# SCH_Sega_Pad_-_Amiga_Joystick_Autofire_2.net
KiCad netlist of a schematic drawn in EasyEDA
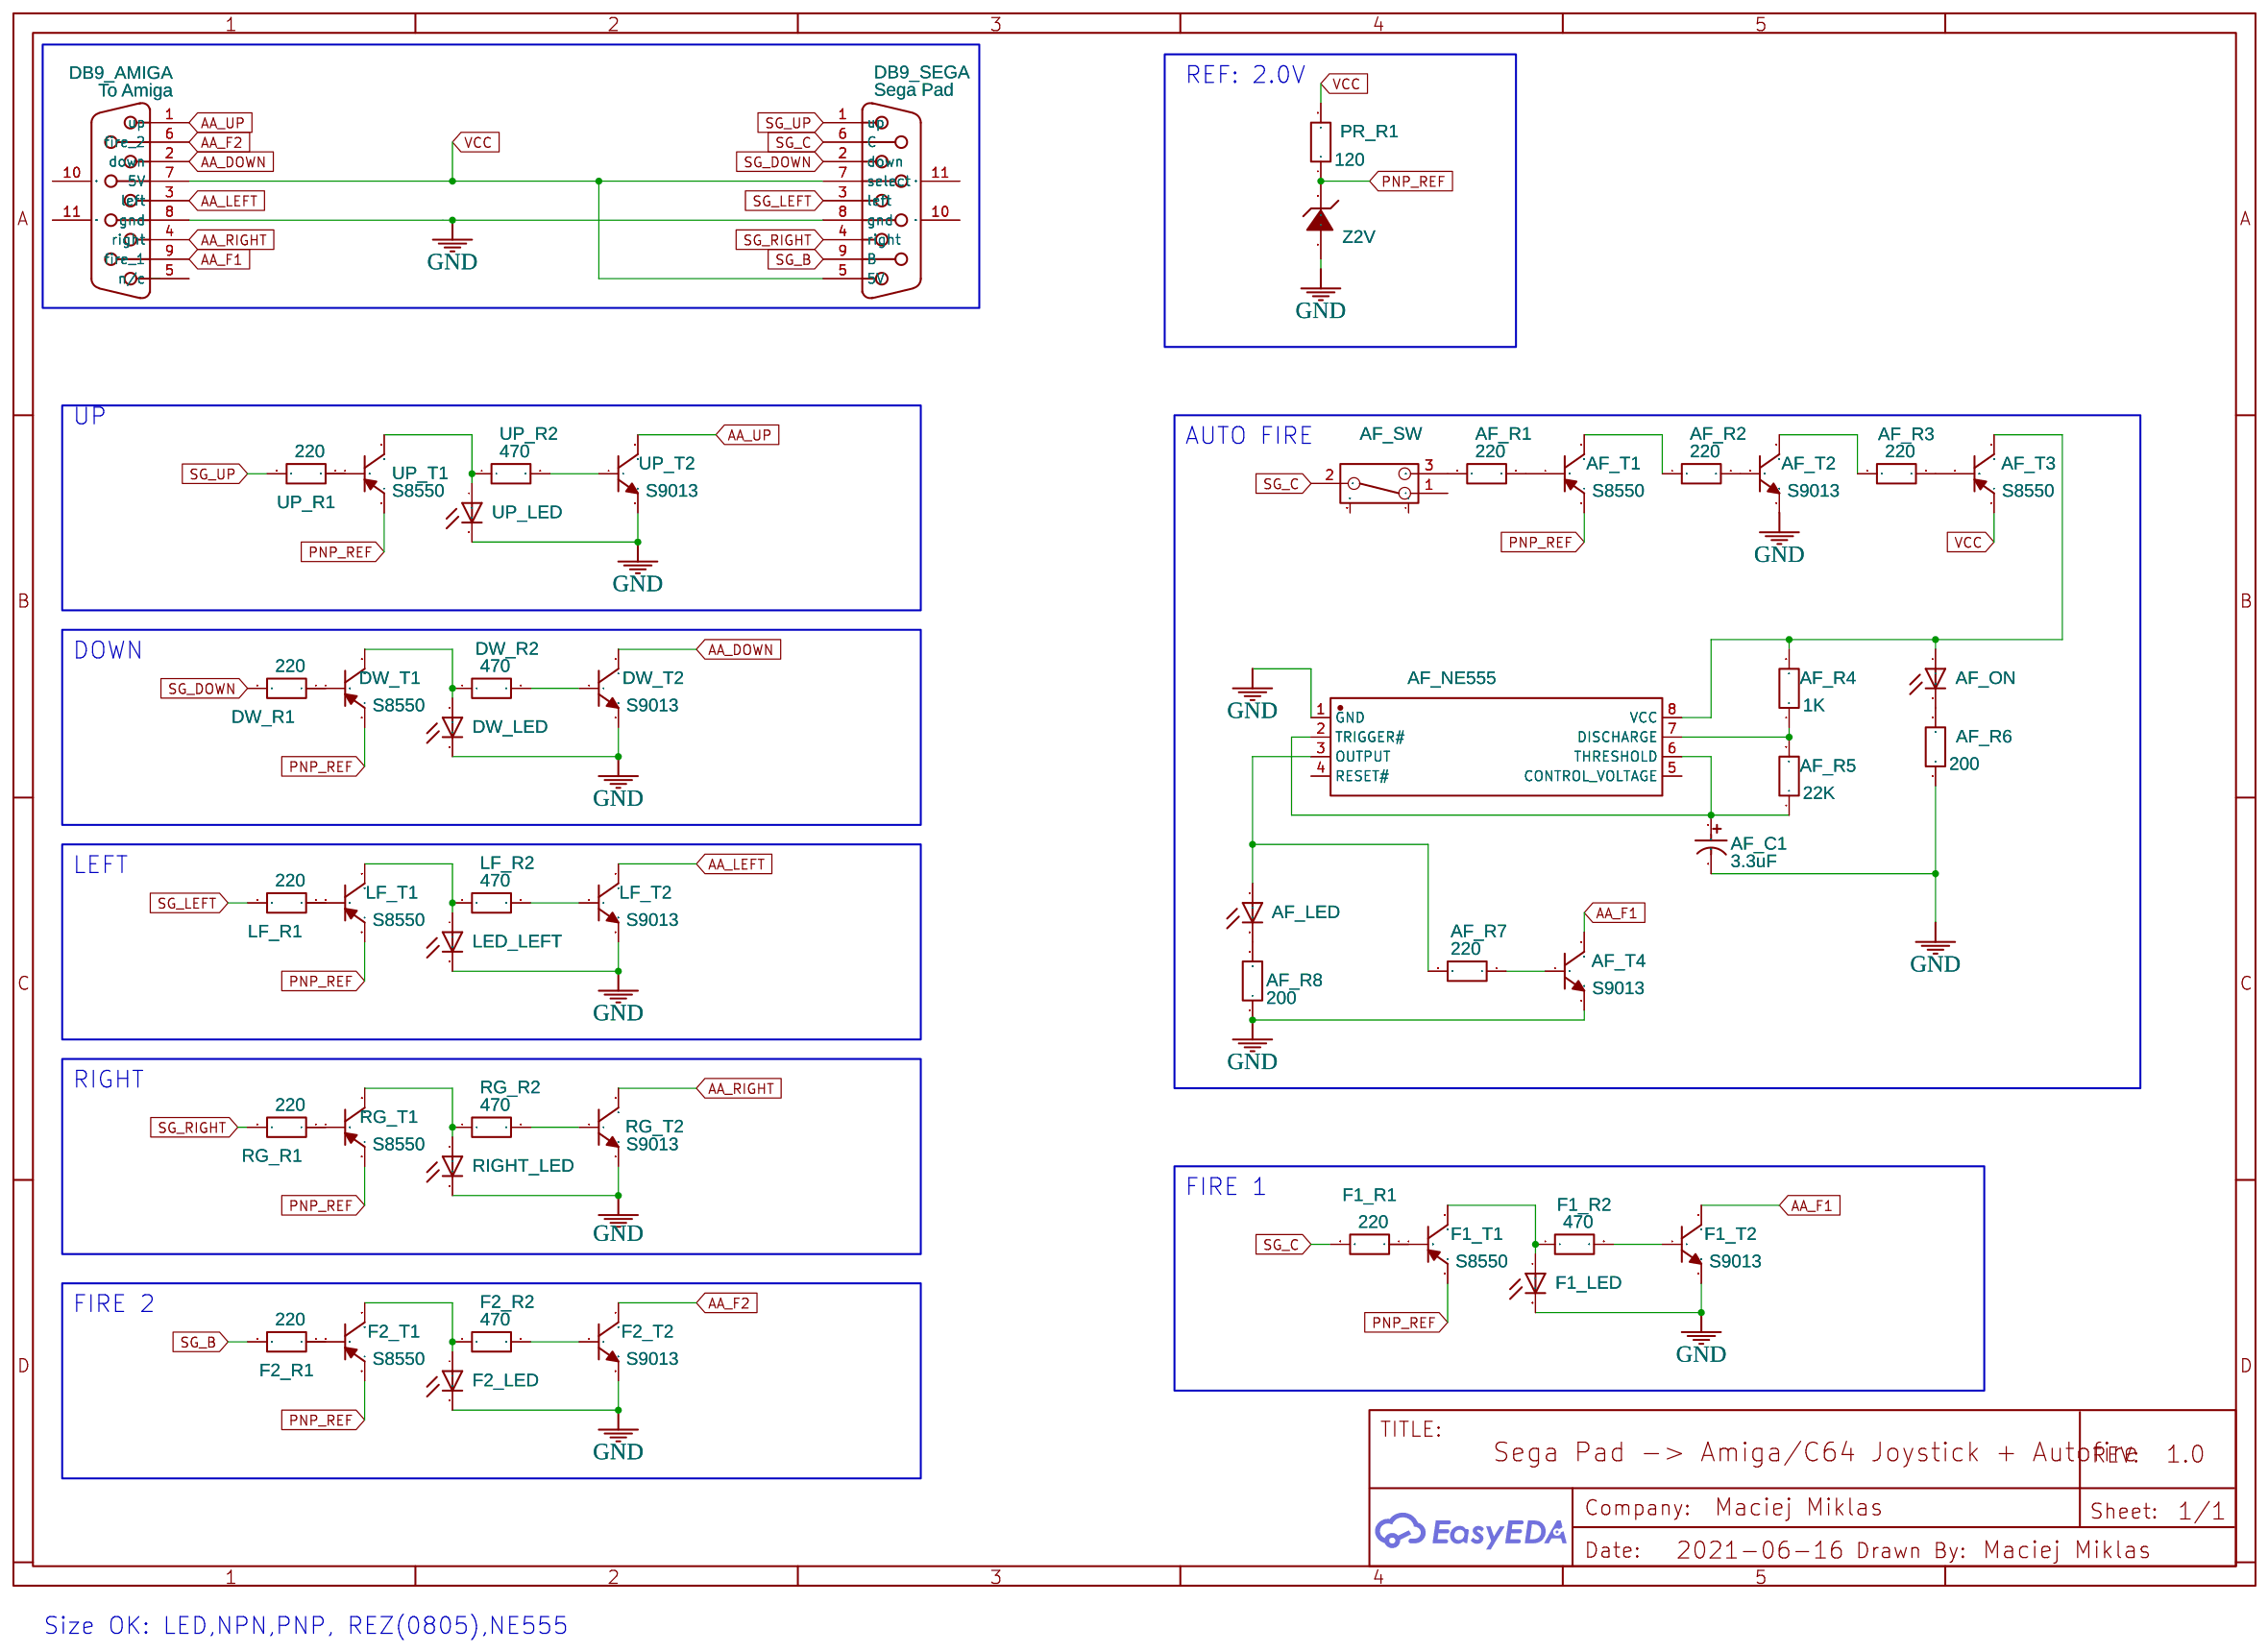
[diagram p0: schematic sheet]

(export (version "E")
  (design (tool "Eeschema 10.0.6"))
  (components
    (comp (ref "AF_555")
      (value "AF_NE555")
      (fields (field (name "BOM_Manufacturer Part") "NE555D") (field (name "BOM_Supplier Part") "C596355"))
      (libsource (lib "") (part "NE555D_C596355"))
    )
    (comp (ref "AF_C1")
      (value "3.3uF")
      (fields
        (field (name "BOM_Manufacturer Part") "3.3uF 50V 5*11")
        (field (name "BOM_Supplier Part") "C45666")
      )
      (libsource (lib "") (part "3.3uF 50V 5*11"))
    )
    (comp (ref "AF_LED") (value "LED") (libsource (lib "") (part "LED_2")))
    (comp (ref "AF_ON") (value "LED") (libsource (lib "") (part "LED_1")))
    (comp (ref "AF_R1")
      (value "220")
      (fields
        (field (name "BOM_Manufacturer Part") "WR08X102 JTL")
        (field (name "BOM_Supplier Part") "C384174")
      )
      (libsource (lib "") (part "WR08X102 JTL_7"))
    )
    (comp (ref "AF_R2")
      (value "220")
      (fields
        (field (name "BOM_Manufacturer Part") "WR08X102 JTL")
        (field (name "BOM_Supplier Part") "C384174")
      )
      (libsource (lib "") (part "WR08X102 JTL_6"))
    )
    (comp (ref "AF_R3")
      (value "220")
      (fields
        (field (name "BOM_Manufacturer Part") "WR08X102 JTL")
        (field (name "BOM_Supplier Part") "C384174")
      )
      (libsource (lib "") (part "WR08X102 JTL_6"))
    )
    (comp (ref "AF_R4")
      (value "1K")
      (fields
        (field (name "BOM_Manufacturer Part") "WR08X102 JTL")
        (field (name "BOM_Supplier Part") "C384174")
      )
      (libsource (lib "") (part "WR08X102 JTL"))
    )
    (comp (ref "AF_R5")
      (value "22K")
      (fields
        (field (name "BOM_Manufacturer Part") "WR08X102 JTL")
        (field (name "BOM_Supplier Part") "C384174")
      )
      (libsource (lib "") (part "WR08X102 JTL"))
    )
    (comp (ref "AF_R6")
      (value "200")
      (fields
        (field (name "BOM_Manufacturer Part") "WR08X102 JTL")
        (field (name "BOM_Supplier Part") "C384174")
      )
      (libsource (lib "") (part "WR08X102 JTL"))
    )
    (comp (ref "AF_R7")
      (value "220")
      (fields
        (field (name "BOM_Manufacturer Part") "WR08X102 JTL")
        (field (name "BOM_Supplier Part") "C384174")
      )
      (libsource (lib "") (part "WR08X102 JTL_7"))
    )
    (comp (ref "AF_R8")
      (value "200")
      (fields
        (field (name "BOM_Manufacturer Part") "WR08X102 JTL")
        (field (name "BOM_Supplier Part") "C384174")
      )
      (libsource (lib "") (part "WR08X102 JTL"))
    )
    (comp (ref "AF_SW") (value "AUTOFIRE ON/OFF") (libsource (lib "") (part "SW_SPDT")))
    (comp (ref "AF_T1")
      (value "S8550")
      (fields (field (name "BOM_Supplier Part") "C2828467"))
      (libsource (lib "") (part "S8550_C2828467_6"))
    )
    (comp (ref "AF_T2")
      (value "S9013")
      (fields
        (field (name "BOM_Manufacturer Part") "S9013 120-200")
        (field (name "BOM_Supplier Part") "C107404")
      )
      (libsource (lib "") (part "S9013 120-200_4"))
    )
    (comp (ref "AF_T3")
      (value "S8550")
      (fields (field (name "BOM_Supplier Part") "C2828467"))
      (libsource (lib "") (part "S8550_C2828467_6"))
    )
    (comp (ref "AF_T4")
      (value "S9013")
      (fields
        (field (name "BOM_Manufacturer Part") "S9013 120-200")
        (field (name "BOM_Supplier Part") "C107404")
      )
      (libsource (lib "") (part "S9013 120-200_4"))
    )
    (comp (ref "DB9_AMIGA")
      (value "To Amiga")
      (fields (field (name "BOM_Supplier Part") "C141882"))
      (libsource (lib "") (part "DB9_Female"))
    )
    (comp (ref "DB9_SEGA")
      (value "Sega Pad")
      (fields (field (name "BOM_Supplier Part") "C185657"))
      (libsource (lib "") (part "DB9_Male"))
    )
    (comp (ref "DW_LED") (value "LED") (libsource (lib "") (part "LED_6")))
    (comp (ref "DW_R1")
      (value "220")
      (fields
        (field (name "BOM_Manufacturer Part") "WR08X102 JTL")
        (field (name "BOM_Supplier Part") "C384174")
      )
      (libsource (lib "") (part "WR08X102 JTL_13"))
    )
    (comp (ref "DW_R2")
      (value "470")
      (fields
        (field (name "BOM_Manufacturer Part") "WR08X102 JTL")
        (field (name "BOM_Supplier Part") "C384174")
      )
      (libsource (lib "") (part "WR08X102 JTL_3"))
    )
    (comp (ref "DW_T1")
      (value "S8550")
      (fields (field (name "BOM_Supplier Part") "C2828467"))
      (libsource (lib "") (part "S8550_C2828467_5"))
    )
    (comp (ref "DW_T2")
      (value "S9013")
      (fields
        (field (name "BOM_Manufacturer Part") "S9013 120-200")
        (field (name "BOM_Supplier Part") "C107404")
      )
      (libsource (lib "") (part "S9013 120-200_6"))
    )
    (comp (ref "F1_LED") (value "LED") (libsource (lib "") (part "LED_7")))
    (comp (ref "F1_R1")
      (value "220")
      (fields
        (field (name "BOM_Manufacturer Part") "WR08X102 JTL")
        (field (name "BOM_Supplier Part") "C384174")
      )
      (libsource (lib "") (part "WR08X102 JTL_14"))
    )
    (comp (ref "F1_R2")
      (value "470")
      (fields
        (field (name "BOM_Manufacturer Part") "WR08X102 JTL")
        (field (name "BOM_Supplier Part") "C384174")
      )
      (libsource (lib "") (part "WR08X102 JTL_1"))
    )
    (comp (ref "F1_T1")
      (value "S8550")
      (fields (field (name "BOM_Supplier Part") "C2828467"))
      (libsource (lib "") (part "S8550_C2828467_4"))
    )
    (comp (ref "F1_T2")
      (value "S9013")
      (fields
        (field (name "BOM_Manufacturer Part") "S9013 120-200")
        (field (name "BOM_Supplier Part") "C107404")
      )
      (libsource (lib "") (part "S9013 120-200_5"))
    )
    (comp (ref "F2_LED") (value "LED") (libsource (lib "") (part "LED_5")))
    (comp (ref "F2_R1")
      (value "220")
      (fields
        (field (name "BOM_Manufacturer Part") "WR08X102 JTL")
        (field (name "BOM_Supplier Part") "C384174")
      )
      (libsource (lib "") (part "WR08X102 JTL_8"))
    )
    (comp (ref "F2_R2")
      (value "470")
      (fields
        (field (name "BOM_Manufacturer Part") "WR08X102 JTL")
        (field (name "BOM_Supplier Part") "C384174")
      )
      (libsource (lib "") (part "WR08X102 JTL_2"))
    )
    (comp (ref "F2_T1")
      (value "S8550")
      (fields (field (name "BOM_Supplier Part") "C2828467"))
      (libsource (lib "") (part "S8550_C2828467_3"))
    )
    (comp (ref "F2_T2")
      (value "S9013")
      (fields
        (field (name "BOM_Manufacturer Part") "S9013 120-200")
        (field (name "BOM_Supplier Part") "C107404")
      )
      (libsource (lib "") (part "S9013 120-200_2"))
    )
    (comp (ref "LED_LEFT") (value "LED") (libsource (lib "") (part "LED_4")))
    (comp (ref "LF_R1")
      (value "220")
      (fields
        (field (name "BOM_Manufacturer Part") "WR08X102 JTL")
        (field (name "BOM_Supplier Part") "C384174")
      )
      (libsource (lib "") (part "WR08X102 JTL_12"))
    )
    (comp (ref "LF_R2")
      (value "470")
      (fields
        (field (name "BOM_Manufacturer Part") "WR08X102 JTL")
        (field (name "BOM_Supplier Part") "C384174")
      )
      (libsource (lib "") (part "WR08X102 JTL_9"))
    )
    (comp (ref "LF_T1")
      (value "S8550")
      (fields (field (name "BOM_Supplier Part") "C2828467"))
      (libsource (lib "") (part "S8550_C2828467"))
    )
    (comp (ref "LF_T2")
      (value "S9013")
      (fields
        (field (name "BOM_Manufacturer Part") "S9013 120-200")
        (field (name "BOM_Supplier Part") "C107404")
      )
      (libsource (lib "") (part "S9013 120-200_1"))
    )
    (comp (ref "PR_D1")
      (value "Z2V")
      (fields (field (name "BOM_Manufacturer Part") "ZMM2V0") (field (name "BOM_Supplier Part") "C8079"))
      (libsource (lib "") (part "ZMM2V0"))
    )
    (comp (ref "PR_R1")
      (value "120")
      (fields
        (field (name "BOM_Manufacturer Part") "WR08X102 JTL")
        (field (name "BOM_Supplier Part") "C384174")
      )
      (libsource (lib "") (part "WR08X102 JTL_10"))
    )
    (comp (ref "RG_R1")
      (value "220")
      (fields
        (field (name "BOM_Manufacturer Part") "WR08X102 JTL")
        (field (name "BOM_Supplier Part") "C384174")
      )
      (libsource (lib "") (part "WR08X102 JTL_5"))
    )
    (comp (ref "RG_R2")
      (value "470")
      (fields
        (field (name "BOM_Manufacturer Part") "WR08X102 JTL")
        (field (name "BOM_Supplier Part") "C384174")
      )
      (libsource (lib "") (part "WR08X102 JTL_11"))
    )
    (comp (ref "RG_T1")
      (value "S8550")
      (fields (field (name "BOM_Supplier Part") "C2828467"))
      (libsource (lib "") (part "S8550_C2828467_1"))
    )
    (comp (ref "RG_T2")
      (value "S9013")
      (fields
        (field (name "BOM_Manufacturer Part") "S9013 120-200")
        (field (name "BOM_Supplier Part") "C107404")
      )
      (libsource (lib "") (part "S9013 120-200"))
    )
    (comp (ref "RIGHT_LED") (value "LED") (libsource (lib "") (part "LED")))
    (comp (ref "UP_LED") (value "LED") (libsource (lib "") (part "LED_3")))
    (comp (ref "UP_R1")
      (value "220")
      (fields
        (field (name "BOM_Manufacturer Part") "WR08X102 JTL")
        (field (name "BOM_Supplier Part") "C384174")
      )
      (libsource (lib "") (part "WR08X102 JTL_15"))
    )
    (comp (ref "UP_R2")
      (value "470")
      (fields
        (field (name "BOM_Manufacturer Part") "WR08X102 JTL")
        (field (name "BOM_Supplier Part") "C384174")
      )
      (libsource (lib "") (part "WR08X102 JTL_4"))
    )
    (comp (ref "UP_T1")
      (value "S8550")
      (fields (field (name "BOM_Supplier Part") "C2828467"))
      (libsource (lib "") (part "S8550_C2828467_2"))
    )
    (comp (ref "UP_T2")
      (value "S9013")
      (fields
        (field (name "BOM_Manufacturer Part") "S9013 120-200")
        (field (name "BOM_Supplier Part") "C107404")
      )
      (libsource (lib "") (part "S9013 120-200_3"))
    )
  )
  (nets
    (net (code "1") (name "AA_DOWN") (class "Default")
      (node (ref "DB9_AMIGA") (pin "2") (pinfunction "down_2") (pintype "input"))
      (node (ref "DW_T2") (pin "3") (pinfunction "3_3") (pintype "input"))
    )
    (net (code "2") (name "AA_F1") (class "Default")
      (node (ref "AF_T4") (pin "3") (pinfunction "3_3") (pintype "input"))
      (node (ref "DB9_AMIGA") (pin "9") (pinfunction "fire_1_9") (pintype "input"))
      (node (ref "F1_T2") (pin "3") (pinfunction "3_3") (pintype "input"))
    )
    (net (code "3") (name "AA_F2") (class "Default")
      (node (ref "DB9_AMIGA") (pin "6") (pinfunction "fire_2_6") (pintype "input"))
      (node (ref "F2_T2") (pin "3") (pinfunction "3_3") (pintype "input"))
    )
    (net (code "4") (name "AA_LEFT") (class "Default")
      (node (ref "DB9_AMIGA") (pin "3") (pinfunction "left_3") (pintype "input"))
      (node (ref "LF_T2") (pin "3") (pinfunction "3_3") (pintype "input"))
    )
    (net (code "5") (name "AA_RIGHT") (class "Default")
      (node (ref "DB9_AMIGA") (pin "4") (pinfunction "right_4") (pintype "input"))
      (node (ref "RG_T2") (pin "3") (pinfunction "3_3") (pintype "input"))
    )
    (net (code "6") (name "AA_UP") (class "Default")
      (node (ref "DB9_AMIGA") (pin "1") (pinfunction "up_1") (pintype "input"))
      (node (ref "UP_T2") (pin "3") (pinfunction "3_3") (pintype "input"))
    )
    (net (code "7") (name "GND") (class "Default")
      (node (ref "AF_555") (pin "1") (pinfunction "GND_1") (pintype "unspecified"))
      (node (ref "AF_C1") (pin "2") (pinfunction "2_2") (pintype "input"))
      (node (ref "AF_R6") (pin "1") (pinfunction "1_1") (pintype "unspecified"))
      (node (ref "AF_R8") (pin "1") (pinfunction "1_1") (pintype "unspecified"))
      (node (ref "AF_T2") (pin "2") (pinfunction "2_2") (pintype "input"))
      (node (ref "AF_T4") (pin "2") (pinfunction "2_2") (pintype "input"))
      (node (ref "DB9_AMIGA") (pin "8") (pinfunction "gnd_8") (pintype "input"))
      (node (ref "DB9_SEGA") (pin "8") (pinfunction "gnd_8") (pintype "input"))
      (node (ref "DW_LED") (pin "C") (pinfunction "C_C") (pintype "unspecified"))
      (node (ref "DW_T2") (pin "2") (pinfunction "2_2") (pintype "input"))
      (node (ref "F1_LED") (pin "C") (pinfunction "C_C") (pintype "unspecified"))
      (node (ref "F1_T2") (pin "2") (pinfunction "2_2") (pintype "input"))
      (node (ref "F2_LED") (pin "C") (pinfunction "C_C") (pintype "unspecified"))
      (node (ref "F2_T2") (pin "2") (pinfunction "2_2") (pintype "input"))
      (node (ref "LED_LEFT") (pin "C") (pinfunction "C_C") (pintype "unspecified"))
      (node (ref "LF_T2") (pin "2") (pinfunction "2_2") (pintype "input"))
      (node (ref "PR_D1") (pin "2") (pinfunction "A_2") (pintype "unspecified"))
      (node (ref "RG_T2") (pin "2") (pinfunction "2_2") (pintype "input"))
      (node (ref "RIGHT_LED") (pin "C") (pinfunction "C_C") (pintype "unspecified"))
      (node (ref "UP_LED") (pin "C") (pinfunction "C_C") (pintype "unspecified"))
      (node (ref "UP_T2") (pin "2") (pinfunction "2_2") (pintype "input"))
    )
    (net (code "8") (name "Net-(AF_555-DISCHARGE)") (class "Default")
      (node (ref "AF_555") (pin "7") (pinfunction "DISCHARGE_7") (pintype "unspecified"))
      (node (ref "AF_R4") (pin "1") (pinfunction "1_1") (pintype "unspecified"))
      (node (ref "AF_R5") (pin "2") (pinfunction "2_2") (pintype "unspecified"))
    )
    (net (code "9") (name "Net-(AF_555-OUTPUT)") (class "Default")
      (node (ref "AF_555") (pin "3") (pinfunction "OUTPUT_3") (pintype "unspecified"))
      (node (ref "AF_LED") (pin "A") (pinfunction "A_A") (pintype "unspecified"))
      (node (ref "AF_R7") (pin "2") (pinfunction "2_2") (pintype "unspecified"))
    )
    (net (code "10") (name "Net-(AF_555-THRESHOLD)") (class "Default")
      (node (ref "AF_555") (pin "2") (pinfunction "TRIGGER#_2") (pintype "unspecified"))
      (node (ref "AF_555") (pin "6") (pinfunction "THRESHOLD_6") (pintype "unspecified"))
      (node (ref "AF_C1") (pin "1") (pinfunction "1_1") (pintype "input"))
      (node (ref "AF_R5") (pin "1") (pinfunction "1_1") (pintype "unspecified"))
    )
    (net (code "11") (name "Net-(AF_555-VCC)") (class "Default")
      (node (ref "AF_555") (pin "8") (pinfunction "VCC_8") (pintype "unspecified"))
      (node (ref "AF_ON") (pin "A") (pinfunction "A_A") (pintype "unspecified"))
      (node (ref "AF_R4") (pin "2") (pinfunction "2_2") (pintype "unspecified"))
      (node (ref "AF_T3") (pin "3") (pinfunction "C_3") (pintype "unspecified"))
    )
    (net (code "12") (name "Net-(AF_LED-PadC)") (class "Default")
      (node (ref "AF_LED") (pin "C") (pinfunction "C_C") (pintype "unspecified"))
      (node (ref "AF_R8") (pin "2") (pinfunction "2_2") (pintype "unspecified"))
    )
    (net (code "13") (name "Net-(AF_ON-PadC)") (class "Default")
      (node (ref "AF_ON") (pin "C") (pinfunction "C_C") (pintype "unspecified"))
      (node (ref "AF_R6") (pin "2") (pinfunction "2_2") (pintype "unspecified"))
    )
    (net (code "14") (name "Net-(AF_R1-Pad2)") (class "Default")
      (node (ref "AF_R1") (pin "2") (pinfunction "2_2") (pintype "unspecified"))
      (node (ref "AF_SW") (pin "3") (pinfunction "3_3") (pintype "unspecified"))
    )
    (net (code "15") (name "Net-(AF_R2-Pad2)") (class "Default")
      (node (ref "AF_R2") (pin "2") (pinfunction "2_2") (pintype "unspecified"))
      (node (ref "AF_T2") (pin "1") (pinfunction "1_1") (pintype "input"))
    )
    (net (code "16") (name "Net-(AF_R3-Pad1)") (class "Default")
      (node (ref "AF_R3") (pin "1") (pinfunction "1_1") (pintype "unspecified"))
      (node (ref "AF_T2") (pin "3") (pinfunction "3_3") (pintype "input"))
    )
    (net (code "17") (name "Net-(AF_R7-Pad1)") (class "Default")
      (node (ref "AF_R7") (pin "1") (pinfunction "1_1") (pintype "unspecified"))
      (node (ref "AF_T4") (pin "1") (pinfunction "1_1") (pintype "input"))
    )
    (net (code "18") (name "Net-(AF_T1-B)") (class "Default")
      (node (ref "AF_R1") (pin "1") (pinfunction "1_1") (pintype "unspecified"))
      (node (ref "AF_T1") (pin "1") (pinfunction "B_1") (pintype "unspecified"))
    )
    (net (code "19") (name "Net-(AF_T1-C)") (class "Default")
      (node (ref "AF_R2") (pin "1") (pinfunction "1_1") (pintype "unspecified"))
      (node (ref "AF_T1") (pin "3") (pinfunction "C_3") (pintype "unspecified"))
    )
    (net (code "20") (name "Net-(AF_T3-B)") (class "Default")
      (node (ref "AF_R3") (pin "2") (pinfunction "2_2") (pintype "unspecified"))
      (node (ref "AF_T3") (pin "1") (pinfunction "B_1") (pintype "unspecified"))
    )
    (net (code "21") (name "Net-(DW_R2-Pad2)") (class "Default")
      (node (ref "DW_R2") (pin "2") (pinfunction "2_2") (pintype "unspecified"))
      (node (ref "DW_T2") (pin "1") (pinfunction "1_1") (pintype "input"))
    )
    (net (code "22") (name "Net-(DW_T1-B)") (class "Default")
      (node (ref "DW_R1") (pin "1") (pinfunction "1_1") (pintype "unspecified"))
      (node (ref "DW_T1") (pin "1") (pinfunction "B_1") (pintype "unspecified"))
    )
    (net (code "23") (name "Net-(DW_T1-C)") (class "Default")
      (node (ref "DW_LED") (pin "A") (pinfunction "A_A") (pintype "unspecified"))
      (node (ref "DW_R2") (pin "1") (pinfunction "1_1") (pintype "unspecified"))
      (node (ref "DW_T1") (pin "3") (pinfunction "C_3") (pintype "unspecified"))
    )
    (net (code "24") (name "Net-(F1_R2-Pad2)") (class "Default")
      (node (ref "F1_R2") (pin "2") (pinfunction "2_2") (pintype "unspecified"))
      (node (ref "F1_T2") (pin "1") (pinfunction "1_1") (pintype "input"))
    )
    (net (code "25") (name "Net-(F1_T1-B)") (class "Default")
      (node (ref "F1_R1") (pin "1") (pinfunction "1_1") (pintype "unspecified"))
      (node (ref "F1_T1") (pin "1") (pinfunction "B_1") (pintype "unspecified"))
    )
    (net (code "26") (name "Net-(F1_T1-C)") (class "Default")
      (node (ref "F1_LED") (pin "A") (pinfunction "A_A") (pintype "unspecified"))
      (node (ref "F1_R2") (pin "1") (pinfunction "1_1") (pintype "unspecified"))
      (node (ref "F1_T1") (pin "3") (pinfunction "C_3") (pintype "unspecified"))
    )
    (net (code "27") (name "Net-(F2_R2-Pad2)") (class "Default")
      (node (ref "F2_R2") (pin "2") (pinfunction "2_2") (pintype "unspecified"))
      (node (ref "F2_T2") (pin "1") (pinfunction "1_1") (pintype "input"))
    )
    (net (code "28") (name "Net-(F2_T1-B)") (class "Default")
      (node (ref "F2_R1") (pin "1") (pinfunction "1_1") (pintype "unspecified"))
      (node (ref "F2_T1") (pin "1") (pinfunction "B_1") (pintype "unspecified"))
    )
    (net (code "29") (name "Net-(F2_T1-C)") (class "Default")
      (node (ref "F2_LED") (pin "A") (pinfunction "A_A") (pintype "unspecified"))
      (node (ref "F2_R2") (pin "1") (pinfunction "1_1") (pintype "unspecified"))
      (node (ref "F2_T1") (pin "3") (pinfunction "C_3") (pintype "unspecified"))
    )
    (net (code "30") (name "Net-(LF_R2-Pad2)") (class "Default")
      (node (ref "LF_R2") (pin "2") (pinfunction "2_2") (pintype "unspecified"))
      (node (ref "LF_T2") (pin "1") (pinfunction "1_1") (pintype "input"))
    )
    (net (code "31") (name "Net-(LF_T1-B)") (class "Default")
      (node (ref "LF_R1") (pin "1") (pinfunction "1_1") (pintype "unspecified"))
      (node (ref "LF_T1") (pin "1") (pinfunction "B_1") (pintype "unspecified"))
    )
    (net (code "32") (name "Net-(LF_T1-C)") (class "Default")
      (node (ref "LED_LEFT") (pin "A") (pinfunction "A_A") (pintype "unspecified"))
      (node (ref "LF_R2") (pin "1") (pinfunction "1_1") (pintype "unspecified"))
      (node (ref "LF_T1") (pin "3") (pinfunction "C_3") (pintype "unspecified"))
    )
    (net (code "33") (name "Net-(RG_R2-Pad2)") (class "Default")
      (node (ref "RG_R2") (pin "2") (pinfunction "2_2") (pintype "unspecified"))
      (node (ref "RG_T2") (pin "1") (pinfunction "1_1") (pintype "input"))
    )
    (net (code "34") (name "Net-(RG_T1-B)") (class "Default")
      (node (ref "RG_R1") (pin "1") (pinfunction "1_1") (pintype "unspecified"))
      (node (ref "RG_T1") (pin "1") (pinfunction "B_1") (pintype "unspecified"))
    )
    (net (code "35") (name "Net-(RG_T1-C)") (class "Default")
      (node (ref "RG_R2") (pin "1") (pinfunction "1_1") (pintype "unspecified"))
      (node (ref "RG_T1") (pin "3") (pinfunction "C_3") (pintype "unspecified"))
      (node (ref "RIGHT_LED") (pin "A") (pinfunction "A_A") (pintype "unspecified"))
    )
    (net (code "36") (name "Net-(UP_R2-Pad2)") (class "Default")
      (node (ref "UP_R2") (pin "2") (pinfunction "2_2") (pintype "unspecified"))
      (node (ref "UP_T2") (pin "1") (pinfunction "1_1") (pintype "input"))
    )
    (net (code "37") (name "Net-(UP_T1-B)") (class "Default")
      (node (ref "UP_R1") (pin "1") (pinfunction "1_1") (pintype "unspecified"))
      (node (ref "UP_T1") (pin "1") (pinfunction "B_1") (pintype "unspecified"))
    )
    (net (code "38") (name "Net-(UP_T1-C)") (class "Default")
      (node (ref "UP_LED") (pin "A") (pinfunction "A_A") (pintype "unspecified"))
      (node (ref "UP_R2") (pin "1") (pinfunction "1_1") (pintype "unspecified"))
      (node (ref "UP_T1") (pin "3") (pinfunction "C_3") (pintype "unspecified"))
    )
    (net (code "39") (name "PNP_REF") (class "Default")
      (node (ref "AF_T1") (pin "2") (pinfunction "E_2") (pintype "unspecified"))
      (node (ref "DW_T1") (pin "2") (pinfunction "E_2") (pintype "unspecified"))
      (node (ref "F1_T1") (pin "2") (pinfunction "E_2") (pintype "unspecified"))
      (node (ref "F2_T1") (pin "2") (pinfunction "E_2") (pintype "unspecified"))
      (node (ref "LF_T1") (pin "2") (pinfunction "E_2") (pintype "unspecified"))
      (node (ref "PR_D1") (pin "1") (pinfunction "C_1") (pintype "unspecified"))
      (node (ref "PR_R1") (pin "1") (pinfunction "1_1") (pintype "unspecified"))
      (node (ref "RG_T1") (pin "2") (pinfunction "E_2") (pintype "unspecified"))
      (node (ref "UP_T1") (pin "2") (pinfunction "E_2") (pintype "unspecified"))
    )
    (net (code "40") (name "SG_B") (class "Default")
      (node (ref "DB9_SEGA") (pin "9") (pinfunction "B_9") (pintype "input"))
      (node (ref "F2_R1") (pin "2") (pinfunction "2_2") (pintype "unspecified"))
    )
    (net (code "41") (name "SG_C") (class "Default")
      (node (ref "AF_SW") (pin "2") (pinfunction "2_2") (pintype "unspecified"))
      (node (ref "DB9_SEGA") (pin "6") (pinfunction "C_6") (pintype "input"))
      (node (ref "F1_R1") (pin "2") (pinfunction "2_2") (pintype "unspecified"))
    )
    (net (code "42") (name "SG_DOWN") (class "Default")
      (node (ref "DB9_SEGA") (pin "2") (pinfunction "down_2") (pintype "input"))
      (node (ref "DW_R1") (pin "2") (pinfunction "2_2") (pintype "unspecified"))
    )
    (net (code "43") (name "SG_LEFT") (class "Default")
      (node (ref "DB9_SEGA") (pin "3") (pinfunction "left_3") (pintype "input"))
      (node (ref "LF_R1") (pin "2") (pinfunction "2_2") (pintype "unspecified"))
    )
    (net (code "44") (name "SG_RIGHT") (class "Default")
      (node (ref "DB9_SEGA") (pin "4") (pinfunction "right_4") (pintype "input"))
      (node (ref "RG_R1") (pin "2") (pinfunction "2_2") (pintype "unspecified"))
    )
    (net (code "45") (name "SG_UP") (class "Default")
      (node (ref "DB9_SEGA") (pin "1") (pinfunction "up_1") (pintype "input"))
      (node (ref "UP_R1") (pin "2") (pinfunction "2_2") (pintype "unspecified"))
    )
    (net (code "46") (name "VCC") (class "Default")
      (node (ref "AF_T3") (pin "2") (pinfunction "E_2") (pintype "unspecified"))
      (node (ref "DB9_AMIGA") (pin "7") (pinfunction "5V_7") (pintype "input"))
      (node (ref "DB9_SEGA") (pin "5") (pinfunction "5V_5") (pintype "input"))
      (node (ref "DB9_SEGA") (pin "7") (pinfunction "select_7") (pintype "input"))
      (node (ref "PR_R1") (pin "2") (pinfunction "2_2") (pintype "unspecified"))
    )
    (net (code "47") (name "unconnected-(AF_555-CONTROL_VOLTAGE-Pad5)") (class "Default")
      (node (ref "AF_555") (pin "5") (pinfunction "CONTROL_VOLTAGE_5") (pintype "unspecified"))
    )
    (net (code "48") (name "unconnected-(AF_555-RESET#-Pad4)") (class "Default")
      (node (ref "AF_555") (pin "4") (pinfunction "RESET#_4") (pintype "unspecified"))
    )
    (net (code "49") (name "unconnected-(AF_SW-Pad1)") (class "Default")
      (node (ref "AF_SW") (pin "1") (pinfunction "1_1") (pintype "unspecified"))
    )
    (net (code "50") (name "unconnected-(AF_SW-Pad4)") (class "Default")
      (node (ref "AF_SW") (pin "4") (pinfunction "4_4") (pintype "unspecified"))
    )
    (net (code "51") (name "unconnected-(AF_SW-Pad5)") (class "Default")
      (node (ref "AF_SW") (pin "5") (pinfunction "5_5") (pintype "unspecified"))
    )
    (net (code "52") (name "unconnected-(DB9_AMIGA-MH1-Pad10)") (class "Default")
      (node (ref "DB9_AMIGA") (pin "10") (pinfunction "MH1_10") (pintype "input"))
    )
    (net (code "53") (name "unconnected-(DB9_AMIGA-MH2-Pad11)") (class "Default")
      (node (ref "DB9_AMIGA") (pin "11") (pinfunction "MH2_11") (pintype "input"))
    )
    (net (code "54") (name "unconnected-(DB9_AMIGA-n{slash}c-Pad5)") (class "Default")
      (node (ref "DB9_AMIGA") (pin "5") (pinfunction "n/c_5") (pintype "input"))
    )
    (net (code "55") (name "unconnected-(DB9_SEGA-MH1-Pad10)") (class "Default")
      (node (ref "DB9_SEGA") (pin "10") (pinfunction "MH1_10") (pintype "input"))
    )
    (net (code "56") (name "unconnected-(DB9_SEGA-MH2-Pad11)") (class "Default")
      (node (ref "DB9_SEGA") (pin "11") (pinfunction "MH2_11") (pintype "input"))
    )
  )
)
